# M1_CM4.net
KiCad netlist of a schematic drawn in Altium Designer
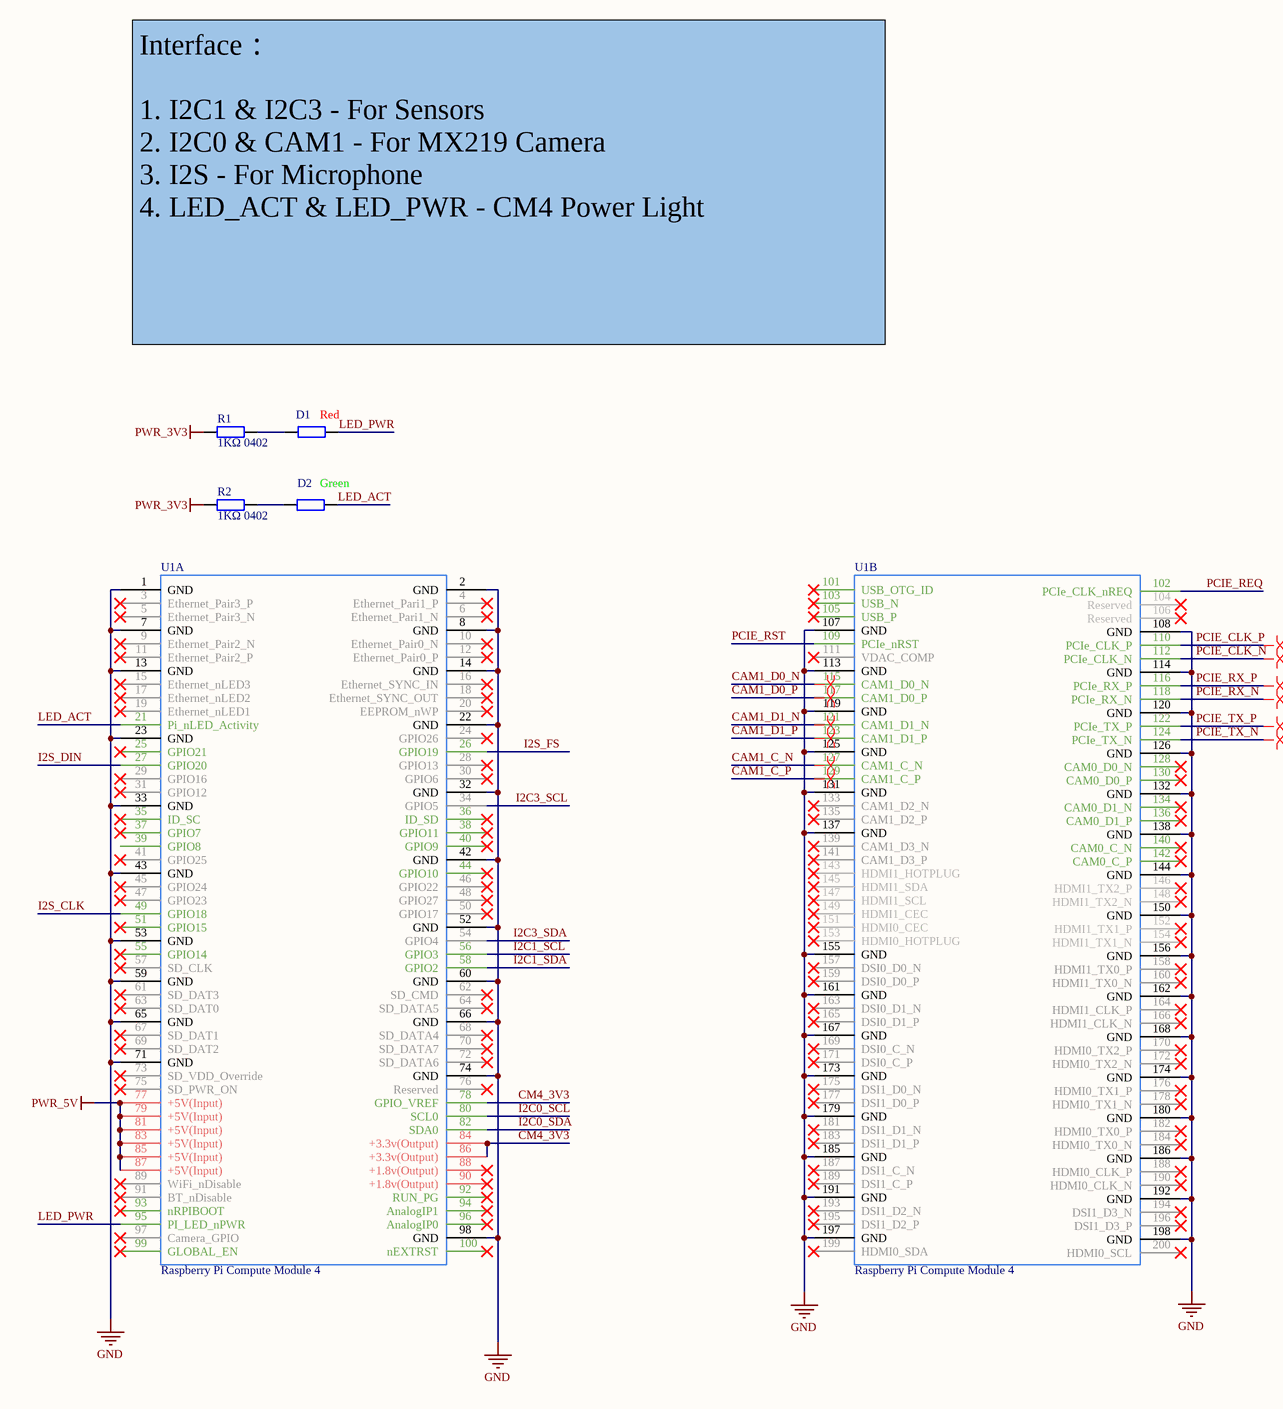
[diagram p0: M1_CM4.SchDoc]

(export (version "E")
  (design (tool "Eeschema 10.0.6"))
  (components
    (comp (ref "D1")
      (value "Red")
      (footprint "0402_R")
      (description "贴片电阻")
      (libsource (lib "Miscellaneous Devices LC") (part "0402 10KΩ (1002) 1%"))
    )
    (comp (ref "D2")
      (value "Green")
      (footprint "0402_R")
      (description "贴片电阻")
      (libsource (lib "Miscellaneous Devices LC") (part "0402 10KΩ (1002) 1%"))
    )
    (comp (ref "R1")
      (value "1KΩ 0402")
      (footprint "0402_R")
      (description "贴片电阻")
      (libsource (lib "Miscellaneous Devices LC") (part "0402 1KΩ (1001) 1%"))
    )
    (comp (ref "R2")
      (value "1KΩ 0402")
      (footprint "0402_R")
      (description "贴片电阻")
      (libsource (lib "Miscellaneous Devices LC") (part "0402 1KΩ (1001) 1%"))
    )
    (comp (ref "U1")
      (value "Raspberry Pi Compute Module 4")
      (footprint "CM4T-DF40HC(3.0)-100DS")
      (libsource (lib "Mars") (part "CM4"))
    )
  )
  (nets
    (net (code "1") (name "/CAM1_C_N") (class "Default")
      (node (ref "U1") (pin "127") (pinfunction "CAM1_C_N_127") (pintype "passive"))
    )
    (net (code "2") (name "/CAM1_C_P") (class "Default")
      (node (ref "U1") (pin "129") (pinfunction "CAM1_C_P_129") (pintype "passive"))
    )
    (net (code "3") (name "/CAM1_D0_N") (class "Default")
      (node (ref "U1") (pin "115") (pinfunction "CAM1_D0_N_115") (pintype "passive"))
    )
    (net (code "4") (name "/CAM1_D0_P") (class "Default")
      (node (ref "U1") (pin "117") (pinfunction "CAM1_D0_P_117") (pintype "passive"))
    )
    (net (code "5") (name "/CAM1_D1_N") (class "Default")
      (node (ref "U1") (pin "121") (pinfunction "CAM1_D1_N_121") (pintype "passive"))
    )
    (net (code "6") (name "/CAM1_D1_P") (class "Default")
      (node (ref "U1") (pin "123") (pinfunction "CAM1_D1_P_123") (pintype "passive"))
    )
    (net (code "7") (name "/CM4_3V3") (class "Default")
      (node (ref "U1") (pin "78") (pinfunction "GPIO_VREF_78") (pintype "passive"))
      (node (ref "U1") (pin "84") (pinfunction "+3.3v(Output)_84") (pintype "passive"))
      (node (ref "U1") (pin "86") (pinfunction "+3.3v(Output)_86") (pintype "passive"))
    )
    (net (code "8") (name "/I2C0_SCL") (class "Default")
      (node (ref "U1") (pin "80") (pinfunction "SCL0_80") (pintype "passive"))
    )
    (net (code "9") (name "/I2C0_SDA") (class "Default")
      (node (ref "U1") (pin "82") (pinfunction "SDA0_82") (pintype "passive"))
    )
    (net (code "10") (name "/I2C1_SCL") (class "Default")
      (node (ref "U1") (pin "56") (pinfunction "GPIO3_56") (pintype "passive"))
    )
    (net (code "11") (name "/I2C1_SDA") (class "Default")
      (node (ref "U1") (pin "58") (pinfunction "GPIO2_58") (pintype "passive"))
    )
    (net (code "12") (name "/I2C3_SCL") (class "Default")
      (node (ref "U1") (pin "34") (pinfunction "GPIO5_34") (pintype "passive"))
    )
    (net (code "13") (name "/I2C3_SDA") (class "Default")
      (node (ref "U1") (pin "54") (pinfunction "GPIO4_54") (pintype "passive"))
    )
    (net (code "14") (name "/I2S_CLK") (class "Default")
      (node (ref "U1") (pin "49") (pinfunction "GPIO18_49") (pintype "passive"))
    )
    (net (code "15") (name "/I2S_DIN") (class "Default")
      (node (ref "U1") (pin "27") (pinfunction "GPIO20_27") (pintype "passive"))
    )
    (net (code "16") (name "/I2S_FS") (class "Default")
      (node (ref "U1") (pin "26") (pinfunction "GPIO19_26") (pintype "passive"))
    )
    (net (code "17") (name "/LED_ACT") (class "Default")
      (node (ref "D2") (pin "2") (pinfunction "2_2") (pintype "passive"))
      (node (ref "U1") (pin "21") (pinfunction "Pi_nLED_Activity_21") (pintype "passive"))
    )
    (net (code "18") (name "/LED_PWR") (class "Default")
      (node (ref "D1") (pin "2") (pinfunction "2_2") (pintype "passive"))
      (node (ref "U1") (pin "95") (pinfunction "PI_LED_nPWR_95") (pintype "passive"))
    )
    (net (code "19") (name "/PCIE_CLK_N") (class "Default")
      (node (ref "U1") (pin "112") (pinfunction "PCIe_CLK_N_112") (pintype "passive"))
    )
    (net (code "20") (name "/PCIE_CLK_P") (class "Default")
      (node (ref "U1") (pin "110") (pinfunction "PCIe_CLK_P_110") (pintype "passive"))
    )
    (net (code "21") (name "/PCIE_REQ") (class "Default")
      (node (ref "U1") (pin "102") (pinfunction "PCIe_CLK_nREQ_102") (pintype "passive"))
    )
    (net (code "22") (name "/PCIE_RST") (class "Default")
      (node (ref "U1") (pin "109") (pinfunction "PCIe_nRST_109") (pintype "passive"))
    )
    (net (code "23") (name "/PCIE_RX_N") (class "Default")
      (node (ref "U1") (pin "118") (pinfunction "PCIe_RX_N_118") (pintype "passive"))
    )
    (net (code "24") (name "/PCIE_RX_P") (class "Default")
      (node (ref "U1") (pin "116") (pinfunction "PCIe_RX_P_116") (pintype "passive"))
    )
    (net (code "25") (name "/PCIE_TX_N") (class "Default")
      (node (ref "U1") (pin "124") (pinfunction "PCIe_TX_N_124") (pintype "passive"))
    )
    (net (code "26") (name "/PCIE_TX_P") (class "Default")
      (node (ref "U1") (pin "122") (pinfunction "PCIe_TX_P_122") (pintype "passive"))
    )
    (net (code "27") (name "GND") (class "Default")
      (node (ref "U1") (pin "1") (pinfunction "GND_1") (pintype "passive"))
      (node (ref "U1") (pin "107") (pinfunction "GND_107") (pintype "passive"))
      (node (ref "U1") (pin "108") (pinfunction "GND_108") (pintype "passive"))
      (node (ref "U1") (pin "113") (pinfunction "GND_113") (pintype "passive"))
      (node (ref "U1") (pin "114") (pinfunction "GND_114") (pintype "passive"))
      (node (ref "U1") (pin "119") (pinfunction "GND_119") (pintype "passive"))
      (node (ref "U1") (pin "120") (pinfunction "GND_120") (pintype "passive"))
      (node (ref "U1") (pin "125") (pinfunction "GND_125") (pintype "passive"))
      (node (ref "U1") (pin "126") (pinfunction "GND_126") (pintype "passive"))
      (node (ref "U1") (pin "13") (pinfunction "GND_13") (pintype "passive"))
      (node (ref "U1") (pin "131") (pinfunction "GND_131") (pintype "passive"))
      (node (ref "U1") (pin "132") (pinfunction "GND_132") (pintype "passive"))
      (node (ref "U1") (pin "137") (pinfunction "GND_137") (pintype "passive"))
      (node (ref "U1") (pin "138") (pinfunction "GND_138") (pintype "passive"))
      (node (ref "U1") (pin "14") (pinfunction "GND_14") (pintype "passive"))
      (node (ref "U1") (pin "144") (pinfunction "GND_144") (pintype "passive"))
      (node (ref "U1") (pin "150") (pinfunction "GND_150") (pintype "passive"))
      (node (ref "U1") (pin "155") (pinfunction "GND_155") (pintype "passive"))
      (node (ref "U1") (pin "156") (pinfunction "GND_156") (pintype "passive"))
      (node (ref "U1") (pin "161") (pinfunction "GND_161") (pintype "passive"))
      (node (ref "U1") (pin "162") (pinfunction "GND_162") (pintype "passive"))
      (node (ref "U1") (pin "167") (pinfunction "GND_167") (pintype "passive"))
      (node (ref "U1") (pin "168") (pinfunction "GND_168") (pintype "passive"))
      (node (ref "U1") (pin "173") (pinfunction "GND_173") (pintype "passive"))
      (node (ref "U1") (pin "174") (pinfunction "GND_174") (pintype "passive"))
      (node (ref "U1") (pin "179") (pinfunction "GND_179") (pintype "passive"))
      (node (ref "U1") (pin "180") (pinfunction "GND_180") (pintype "passive"))
      (node (ref "U1") (pin "185") (pinfunction "GND_185") (pintype "passive"))
      (node (ref "U1") (pin "186") (pinfunction "GND_186") (pintype "passive"))
      (node (ref "U1") (pin "191") (pinfunction "GND_191") (pintype "passive"))
      (node (ref "U1") (pin "192") (pinfunction "GND_192") (pintype "passive"))
      (node (ref "U1") (pin "197") (pinfunction "GND_197") (pintype "passive"))
      (node (ref "U1") (pin "198") (pinfunction "GND_198") (pintype "passive"))
      (node (ref "U1") (pin "2") (pinfunction "GND_2") (pintype "passive"))
      (node (ref "U1") (pin "22") (pinfunction "GND_22") (pintype "passive"))
      (node (ref "U1") (pin "23") (pinfunction "GND_23") (pintype "passive"))
      (node (ref "U1") (pin "32") (pinfunction "GND_32") (pintype "passive"))
      (node (ref "U1") (pin "33") (pinfunction "GND_33") (pintype "passive"))
      (node (ref "U1") (pin "42") (pinfunction "GND_42") (pintype "passive"))
      (node (ref "U1") (pin "43") (pinfunction "GND_43") (pintype "passive"))
      (node (ref "U1") (pin "52") (pinfunction "GND_52") (pintype "passive"))
      (node (ref "U1") (pin "53") (pinfunction "GND_53") (pintype "passive"))
      (node (ref "U1") (pin "59") (pinfunction "GND_59") (pintype "passive"))
      (node (ref "U1") (pin "60") (pinfunction "GND_60") (pintype "passive"))
      (node (ref "U1") (pin "65") (pinfunction "GND_65") (pintype "passive"))
      (node (ref "U1") (pin "66") (pinfunction "GND_66") (pintype "passive"))
      (node (ref "U1") (pin "7") (pinfunction "GND_7") (pintype "passive"))
      (node (ref "U1") (pin "71") (pinfunction "GND_71") (pintype "passive"))
      (node (ref "U1") (pin "74") (pinfunction "GND_74") (pintype "passive"))
      (node (ref "U1") (pin "8") (pinfunction "GND_8") (pintype "passive"))
      (node (ref "U1") (pin "98") (pinfunction "GND_98") (pintype "passive"))
    )
    (net (code "28") (name "Net-(D1-Pad1)") (class "Default")
      (node (ref "D1") (pin "1") (pinfunction "1_1") (pintype "passive"))
      (node (ref "R1") (pin "2") (pinfunction "2_2") (pintype "passive"))
    )
    (net (code "29") (name "Net-(D2-Pad1)") (class "Default")
      (node (ref "D2") (pin "1") (pinfunction "1_1") (pintype "passive"))
      (node (ref "R2") (pin "2") (pinfunction "2_2") (pintype "passive"))
    )
    (net (code "30") (name "PWR_3V3") (class "Default")
      (node (ref "R1") (pin "1") (pinfunction "1_1") (pintype "passive"))
      (node (ref "R2") (pin "1") (pinfunction "1_1") (pintype "passive"))
    )
    (net (code "31") (name "PWR_5V") (class "Default")
      (node (ref "U1") (pin "77") (pinfunction "+5V(Input)_77") (pintype "passive"))
      (node (ref "U1") (pin "79") (pinfunction "+5V(Input)_79") (pintype "passive"))
      (node (ref "U1") (pin "81") (pinfunction "+5V(Input)_81") (pintype "passive"))
      (node (ref "U1") (pin "83") (pinfunction "+5V(Input)_83") (pintype "passive"))
      (node (ref "U1") (pin "85") (pinfunction "+5V(Input)_85") (pintype "passive"))
      (node (ref "U1") (pin "87") (pinfunction "+5V(Input)_87") (pintype "passive"))
    )
    (net (code "32") (name "unconnected-(U1A-+1.8v(Output)-Pad88)") (class "Default")
      (node (ref "U1") (pin "88") (pinfunction "+1.8v(Output)_88") (pintype "passive+no_connect"))
    )
    (net (code "33") (name "unconnected-(U1A-+1.8v(Output)-Pad90)") (class "Default")
      (node (ref "U1") (pin "90") (pinfunction "+1.8v(Output)_90") (pintype "passive+no_connect"))
    )
    (net (code "34") (name "unconnected-(U1A-AnalogIP0-Pad96)") (class "Default")
      (node (ref "U1") (pin "96") (pinfunction "AnalogIP0_96") (pintype "passive+no_connect"))
    )
    (net (code "35") (name "unconnected-(U1A-AnalogIP1-Pad94)") (class "Default")
      (node (ref "U1") (pin "94") (pinfunction "AnalogIP1_94") (pintype "passive+no_connect"))
    )
    (net (code "36") (name "unconnected-(U1A-BT_nDisable-Pad91)") (class "Default")
      (node (ref "U1") (pin "91") (pinfunction "BT_nDisable_91") (pintype "passive+no_connect"))
    )
    (net (code "37") (name "unconnected-(U1A-Camera_GPIO-Pad97)") (class "Default")
      (node (ref "U1") (pin "97") (pinfunction "Camera_GPIO_97") (pintype "passive+no_connect"))
    )
    (net (code "38") (name "unconnected-(U1A-EEPROM_nWP-Pad20)") (class "Default")
      (node (ref "U1") (pin "20") (pinfunction "EEPROM_nWP_20") (pintype "passive+no_connect"))
    )
    (net (code "39") (name "unconnected-(U1A-Ethernet_Pair0_N-Pad10)") (class "Default")
      (node (ref "U1") (pin "10") (pinfunction "Ethernet_Pair0_N_10") (pintype "passive+no_connect"))
    )
    (net (code "40") (name "unconnected-(U1A-Ethernet_Pair0_P-Pad12)") (class "Default")
      (node (ref "U1") (pin "12") (pinfunction "Ethernet_Pair0_P_12") (pintype "passive+no_connect"))
    )
    (net (code "41") (name "unconnected-(U1A-Ethernet_Pair2_N-Pad9)") (class "Default")
      (node (ref "U1") (pin "9") (pinfunction "Ethernet_Pair2_N_9") (pintype "passive+no_connect"))
    )
    (net (code "42") (name "unconnected-(U1A-Ethernet_Pair2_P-Pad11)") (class "Default")
      (node (ref "U1") (pin "11") (pinfunction "Ethernet_Pair2_P_11") (pintype "passive+no_connect"))
    )
    (net (code "43") (name "unconnected-(U1A-Ethernet_Pair3_N-Pad5)") (class "Default")
      (node (ref "U1") (pin "5") (pinfunction "Ethernet_Pair3_N_5") (pintype "passive+no_connect"))
    )
    (net (code "44") (name "unconnected-(U1A-Ethernet_Pair3_P-Pad3)") (class "Default")
      (node (ref "U1") (pin "3") (pinfunction "Ethernet_Pair3_P_3") (pintype "passive+no_connect"))
    )
    (net (code "45") (name "unconnected-(U1A-Ethernet_Pari1_N-Pad6)") (class "Default")
      (node (ref "U1") (pin "6") (pinfunction "Ethernet_Pari1_N_6") (pintype "passive+no_connect"))
    )
    (net (code "46") (name "unconnected-(U1A-Ethernet_Pari1_P-Pad4)") (class "Default")
      (node (ref "U1") (pin "4") (pinfunction "Ethernet_Pari1_P_4") (pintype "passive+no_connect"))
    )
    (net (code "47") (name "unconnected-(U1A-Ethernet_SYNC_IN-Pad16)") (class "Default")
      (node (ref "U1") (pin "16") (pinfunction "Ethernet_SYNC_IN_16") (pintype "passive+no_connect"))
    )
    (net (code "48") (name "unconnected-(U1A-Ethernet_SYNC_OUT-Pad18)") (class "Default")
      (node (ref "U1") (pin "18") (pinfunction "Ethernet_SYNC_OUT_18") (pintype "passive+no_connect"))
    )
    (net (code "49") (name "unconnected-(U1A-Ethernet_nLED1-Pad19)") (class "Default")
      (node (ref "U1") (pin "19") (pinfunction "Ethernet_nLED1_19") (pintype "passive+no_connect"))
    )
    (net (code "50") (name "unconnected-(U1A-Ethernet_nLED2-Pad17)") (class "Default")
      (node (ref "U1") (pin "17") (pinfunction "Ethernet_nLED2_17") (pintype "passive+no_connect"))
    )
    (net (code "51") (name "unconnected-(U1A-Ethernet_nLED3-Pad15)") (class "Default")
      (node (ref "U1") (pin "15") (pinfunction "Ethernet_nLED3_15") (pintype "passive+no_connect"))
    )
    (net (code "52") (name "unconnected-(U1A-GLOBAL_EN-Pad99)") (class "Default")
      (node (ref "U1") (pin "99") (pinfunction "GLOBAL_EN_99") (pintype "passive+no_connect"))
    )
    (net (code "53") (name "unconnected-(U1A-GPIO6-Pad30)") (class "Default")
      (node (ref "U1") (pin "30") (pinfunction "GPIO6_30") (pintype "passive+no_connect"))
    )
    (net (code "54") (name "unconnected-(U1A-GPIO7-Pad37)") (class "Default")
      (node (ref "U1") (pin "37") (pinfunction "GPIO7_37") (pintype "passive+no_connect"))
    )
    (net (code "55") (name "unconnected-(U1A-GPIO8-Pad39)") (class "Default")
      (node (ref "U1") (pin "39") (pinfunction "GPIO8_39") (pintype "passive"))
    )
    (net (code "56") (name "unconnected-(U1A-GPIO9-Pad40)") (class "Default")
      (node (ref "U1") (pin "40") (pinfunction "GPIO9_40") (pintype "passive+no_connect"))
    )
    (net (code "57") (name "unconnected-(U1A-GPIO10-Pad44)") (class "Default")
      (node (ref "U1") (pin "44") (pinfunction "GPIO10_44") (pintype "passive+no_connect"))
    )
    (net (code "58") (name "unconnected-(U1A-GPIO11-Pad38)") (class "Default")
      (node (ref "U1") (pin "38") (pinfunction "GPIO11_38") (pintype "passive+no_connect"))
    )
    (net (code "59") (name "unconnected-(U1A-GPIO12-Pad31)") (class "Default")
      (node (ref "U1") (pin "31") (pinfunction "GPIO12_31") (pintype "passive+no_connect"))
    )
    (net (code "60") (name "unconnected-(U1A-GPIO13-Pad28)") (class "Default")
      (node (ref "U1") (pin "28") (pinfunction "GPIO13_28") (pintype "passive+no_connect"))
    )
    (net (code "61") (name "unconnected-(U1A-GPIO14-Pad55)") (class "Default")
      (node (ref "U1") (pin "55") (pinfunction "GPIO14_55") (pintype "passive+no_connect"))
    )
    (net (code "62") (name "unconnected-(U1A-GPIO15-Pad51)") (class "Default")
      (node (ref "U1") (pin "51") (pinfunction "GPIO15_51") (pintype "passive+no_connect"))
    )
    (net (code "63") (name "unconnected-(U1A-GPIO16-Pad29)") (class "Default")
      (node (ref "U1") (pin "29") (pinfunction "GPIO16_29") (pintype "passive+no_connect"))
    )
    (net (code "64") (name "unconnected-(U1A-GPIO17-Pad50)") (class "Default")
      (node (ref "U1") (pin "50") (pinfunction "GPIO17_50") (pintype "passive+no_connect"))
    )
    (net (code "65") (name "unconnected-(U1A-GPIO21-Pad25)") (class "Default")
      (node (ref "U1") (pin "25") (pinfunction "GPIO21_25") (pintype "passive+no_connect"))
    )
    (net (code "66") (name "unconnected-(U1A-GPIO22-Pad46)") (class "Default")
      (node (ref "U1") (pin "46") (pinfunction "GPIO22_46") (pintype "passive+no_connect"))
    )
    (net (code "67") (name "unconnected-(U1A-GPIO23-Pad47)") (class "Default")
      (node (ref "U1") (pin "47") (pinfunction "GPIO23_47") (pintype "passive+no_connect"))
    )
    (net (code "68") (name "unconnected-(U1A-GPIO24-Pad45)") (class "Default")
      (node (ref "U1") (pin "45") (pinfunction "GPIO24_45") (pintype "passive+no_connect"))
    )
    (net (code "69") (name "unconnected-(U1A-GPIO25-Pad41)") (class "Default")
      (node (ref "U1") (pin "41") (pinfunction "GPIO25_41") (pintype "passive+no_connect"))
    )
    (net (code "70") (name "unconnected-(U1A-GPIO26-Pad24)") (class "Default")
      (node (ref "U1") (pin "24") (pinfunction "GPIO26_24") (pintype "passive+no_connect"))
    )
    (net (code "71") (name "unconnected-(U1A-GPIO27-Pad48)") (class "Default")
      (node (ref "U1") (pin "48") (pinfunction "GPIO27_48") (pintype "passive+no_connect"))
    )
    (net (code "72") (name "unconnected-(U1A-ID_SC-Pad35)") (class "Default")
      (node (ref "U1") (pin "35") (pinfunction "ID_SC_35") (pintype "passive+no_connect"))
    )
    (net (code "73") (name "unconnected-(U1A-ID_SD-Pad36)") (class "Default")
      (node (ref "U1") (pin "36") (pinfunction "ID_SD_36") (pintype "passive+no_connect"))
    )
    (net (code "74") (name "unconnected-(U1A-RUN_PG-Pad92)") (class "Default")
      (node (ref "U1") (pin "92") (pinfunction "RUN_PG_92") (pintype "passive+no_connect"))
    )
    (net (code "75") (name "unconnected-(U1A-Reserved-Pad76)") (class "Default")
      (node (ref "U1") (pin "76") (pinfunction "Reserved_76") (pintype "passive+no_connect"))
    )
    (net (code "76") (name "unconnected-(U1A-SD_CLK-Pad57)") (class "Default")
      (node (ref "U1") (pin "57") (pinfunction "SD_CLK_57") (pintype "passive+no_connect"))
    )
    (net (code "77") (name "unconnected-(U1A-SD_CMD-Pad62)") (class "Default")
      (node (ref "U1") (pin "62") (pinfunction "SD_CMD_62") (pintype "passive+no_connect"))
    )
    (net (code "78") (name "unconnected-(U1A-SD_DAT0-Pad63)") (class "Default")
      (node (ref "U1") (pin "63") (pinfunction "SD_DAT0_63") (pintype "passive+no_connect"))
    )
    (net (code "79") (name "unconnected-(U1A-SD_DAT1-Pad67)") (class "Default")
      (node (ref "U1") (pin "67") (pinfunction "SD_DAT1_67") (pintype "passive+no_connect"))
    )
    (net (code "80") (name "unconnected-(U1A-SD_DAT2-Pad69)") (class "Default")
      (node (ref "U1") (pin "69") (pinfunction "SD_DAT2_69") (pintype "passive+no_connect"))
    )
    (net (code "81") (name "unconnected-(U1A-SD_DAT3-Pad61)") (class "Default")
      (node (ref "U1") (pin "61") (pinfunction "SD_DAT3_61") (pintype "passive+no_connect"))
    )
    (net (code "82") (name "unconnected-(U1A-SD_DATA4-Pad68)") (class "Default")
      (node (ref "U1") (pin "68") (pinfunction "SD_DATA4_68") (pintype "passive+no_connect"))
    )
    (net (code "83") (name "unconnected-(U1A-SD_DATA5-Pad64)") (class "Default")
      (node (ref "U1") (pin "64") (pinfunction "SD_DATA5_64") (pintype "passive+no_connect"))
    )
    (net (code "84") (name "unconnected-(U1A-SD_DATA6-Pad72)") (class "Default")
      (node (ref "U1") (pin "72") (pinfunction "SD_DATA6_72") (pintype "passive+no_connect"))
    )
    (net (code "85") (name "unconnected-(U1A-SD_DATA7-Pad70)") (class "Default")
      (node (ref "U1") (pin "70") (pinfunction "SD_DATA7_70") (pintype "passive+no_connect"))
    )
    (net (code "86") (name "unconnected-(U1A-SD_PWR_ON-Pad75)") (class "Default")
      (node (ref "U1") (pin "75") (pinfunction "SD_PWR_ON_75") (pintype "passive+no_connect"))
    )
    (net (code "87") (name "unconnected-(U1A-SD_VDD_Override-Pad73)") (class "Default")
      (node (ref "U1") (pin "73") (pinfunction "SD_VDD_Override_73") (pintype "passive+no_connect"))
    )
    (net (code "88") (name "unconnected-(U1A-WiFi_nDisable-Pad89)") (class "Default")
      (node (ref "U1") (pin "89") (pinfunction "WiFi_nDisable_89") (pintype "passive+no_connect"))
    )
    (net (code "89") (name "unconnected-(U1A-nEXTRST-Pad100)") (class "Default")
      (node (ref "U1") (pin "100") (pinfunction "nEXTRST_100") (pintype "passive+no_connect"))
    )
    (net (code "90") (name "unconnected-(U1A-nRPIBOOT-Pad93)") (class "Default")
      (node (ref "U1") (pin "93") (pinfunction "nRPIBOOT_93") (pintype "passive+no_connect"))
    )
    (net (code "91") (name "unconnected-(U1B-CAM0_C_N-Pad140)") (class "Default")
      (node (ref "U1") (pin "140") (pinfunction "CAM0_C_N_140") (pintype "passive+no_connect"))
    )
    (net (code "92") (name "unconnected-(U1B-CAM0_C_P-Pad142)") (class "Default")
      (node (ref "U1") (pin "142") (pinfunction "CAM0_C_P_142") (pintype "passive+no_connect"))
    )
    (net (code "93") (name "unconnected-(U1B-CAM0_D0_N-Pad128)") (class "Default")
      (node (ref "U1") (pin "128") (pinfunction "CAM0_D0_N_128") (pintype "passive+no_connect"))
    )
    (net (code "94") (name "unconnected-(U1B-CAM0_D0_P-Pad130)") (class "Default")
      (node (ref "U1") (pin "130") (pinfunction "CAM0_D0_P_130") (pintype "passive+no_connect"))
    )
    (net (code "95") (name "unconnected-(U1B-CAM0_D1_N-Pad134)") (class "Default")
      (node (ref "U1") (pin "134") (pinfunction "CAM0_D1_N_134") (pintype "passive+no_connect"))
    )
    (net (code "96") (name "unconnected-(U1B-CAM0_D1_P-Pad136)") (class "Default")
      (node (ref "U1") (pin "136") (pinfunction "CAM0_D1_P_136") (pintype "passive+no_connect"))
    )
    (net (code "97") (name "unconnected-(U1B-CAM1_D2_N-Pad133)") (class "Default")
      (node (ref "U1") (pin "133") (pinfunction "CAM1_D2_N_133") (pintype "passive+no_connect"))
    )
    (net (code "98") (name "unconnected-(U1B-CAM1_D2_P-Pad135)") (class "Default")
      (node (ref "U1") (pin "135") (pinfunction "CAM1_D2_P_135") (pintype "passive+no_connect"))
    )
    (net (code "99") (name "unconnected-(U1B-CAM1_D3_N-Pad139)") (class "Default")
      (node (ref "U1") (pin "139") (pinfunction "CAM1_D3_N_139") (pintype "passive+no_connect"))
    )
    (net (code "100") (name "unconnected-(U1B-CAM1_D3_P-Pad141)") (class "Default")
      (node (ref "U1") (pin "141") (pinfunction "CAM1_D3_P_141") (pintype "passive+no_connect"))
    )
    (net (code "101") (name "unconnected-(U1B-DSI0_C_N-Pad169)") (class "Default")
      (node (ref "U1") (pin "169") (pinfunction "DSI0_C_N_169") (pintype "passive+no_connect"))
    )
    (net (code "102") (name "unconnected-(U1B-DSI0_C_P-Pad171)") (class "Default")
      (node (ref "U1") (pin "171") (pinfunction "DSI0_C_P_171") (pintype "passive+no_connect"))
    )
    (net (code "103") (name "unconnected-(U1B-DSI0_D0_N-Pad157)") (class "Default")
      (node (ref "U1") (pin "157") (pinfunction "DSI0_D0_N_157") (pintype "passive+no_connect"))
    )
    (net (code "104") (name "unconnected-(U1B-DSI0_D0_P-Pad159)") (class "Default")
      (node (ref "U1") (pin "159") (pinfunction "DSI0_D0_P_159") (pintype "passive+no_connect"))
    )
    (net (code "105") (name "unconnected-(U1B-DSI0_D1_N-Pad163)") (class "Default")
      (node (ref "U1") (pin "163") (pinfunction "DSI0_D1_N_163") (pintype "passive+no_connect"))
    )
    (net (code "106") (name "unconnected-(U1B-DSI0_D1_P-Pad165)") (class "Default")
      (node (ref "U1") (pin "165") (pinfunction "DSI0_D1_P_165") (pintype "passive+no_connect"))
    )
    (net (code "107") (name "unconnected-(U1B-DSI1_C_N-Pad187)") (class "Default")
      (node (ref "U1") (pin "187") (pinfunction "DSI1_C_N_187") (pintype "passive+no_connect"))
    )
    (net (code "108") (name "unconnected-(U1B-DSI1_C_P-Pad189)") (class "Default")
      (node (ref "U1") (pin "189") (pinfunction "DSI1_C_P_189") (pintype "passive+no_connect"))
    )
    (net (code "109") (name "unconnected-(U1B-DSI1_D0_N-Pad175)") (class "Default")
      (node (ref "U1") (pin "175") (pinfunction "DSI1_D0_N_175") (pintype "passive+no_connect"))
    )
    (net (code "110") (name "unconnected-(U1B-DSI1_D0_P-Pad177)") (class "Default")
      (node (ref "U1") (pin "177") (pinfunction "DSI1_D0_P_177") (pintype "passive+no_connect"))
    )
    (net (code "111") (name "unconnected-(U1B-DSI1_D1_N-Pad181)") (class "Default")
      (node (ref "U1") (pin "181") (pinfunction "DSI1_D1_N_181") (pintype "passive+no_connect"))
    )
    (net (code "112") (name "unconnected-(U1B-DSI1_D1_P-Pad183)") (class "Default")
      (node (ref "U1") (pin "183") (pinfunction "DSI1_D1_P_183") (pintype "passive+no_connect"))
    )
    (net (code "113") (name "unconnected-(U1B-DSI1_D2_N-Pad193)") (class "Default")
      (node (ref "U1") (pin "193") (pinfunction "DSI1_D2_N_193") (pintype "passive+no_connect"))
    )
    (net (code "114") (name "unconnected-(U1B-DSI1_D2_P-Pad195)") (class "Default")
      (node (ref "U1") (pin "195") (pinfunction "DSI1_D2_P_195") (pintype "passive+no_connect"))
    )
    (net (code "115") (name "unconnected-(U1B-DSI1_D3_N-Pad194)") (class "Default")
      (node (ref "U1") (pin "194") (pinfunction "DSI1_D3_N_194") (pintype "passive+no_connect"))
    )
    (net (code "116") (name "unconnected-(U1B-DSI1_D3_P-Pad196)") (class "Default")
      (node (ref "U1") (pin "196") (pinfunction "DSI1_D3_P_196") (pintype "passive+no_connect"))
    )
    (net (code "117") (name "unconnected-(U1B-HDMI0_CEC-Pad151)") (class "Default")
      (node (ref "U1") (pin "151") (pinfunction "HDMI0_CEC_151") (pintype "passive+no_connect"))
    )
    (net (code "118") (name "unconnected-(U1B-HDMI0_CLK_N-Pad190)") (class "Default")
      (node (ref "U1") (pin "190") (pinfunction "HDMI0_CLK_N_190") (pintype "passive+no_connect"))
    )
    (net (code "119") (name "unconnected-(U1B-HDMI0_CLK_P-Pad188)") (class "Default")
      (node (ref "U1") (pin "188") (pinfunction "HDMI0_CLK_P_188") (pintype "passive+no_connect"))
    )
    (net (code "120") (name "unconnected-(U1B-HDMI0_HOTPLUG-Pad153)") (class "Default")
      (node (ref "U1") (pin "153") (pinfunction "HDMI0_HOTPLUG_153") (pintype "passive+no_connect"))
    )
    (net (code "121") (name "unconnected-(U1B-HDMI0_SCL-Pad200)") (class "Default")
      (node (ref "U1") (pin "200") (pinfunction "HDMI0_SCL_200") (pintype "passive+no_connect"))
    )
    (net (code "122") (name "unconnected-(U1B-HDMI0_SDA-Pad199)") (class "Default")
      (node (ref "U1") (pin "199") (pinfunction "HDMI0_SDA_199") (pintype "passive+no_connect"))
    )
    (net (code "123") (name "unconnected-(U1B-HDMI0_TX0_N-Pad184)") (class "Default")
      (node (ref "U1") (pin "184") (pinfunction "HDMI0_TX0_N_184") (pintype "passive+no_connect"))
    )
    (net (code "124") (name "unconnected-(U1B-HDMI0_TX0_P-Pad182)") (class "Default")
      (node (ref "U1") (pin "182") (pinfunction "HDMI0_TX0_P_182") (pintype "passive+no_connect"))
    )
    (net (code "125") (name "unconnected-(U1B-HDMI0_TX1_N-Pad178)") (class "Default")
      (node (ref "U1") (pin "178") (pinfunction "HDMI0_TX1_N_178") (pintype "passive+no_connect"))
    )
    (net (code "126") (name "unconnected-(U1B-HDMI0_TX1_P-Pad176)") (class "Default")
      (node (ref "U1") (pin "176") (pinfunction "HDMI0_TX1_P_176") (pintype "passive+no_connect"))
    )
    (net (code "127") (name "unconnected-(U1B-HDMI0_TX2_N-Pad172)") (class "Default")
      (node (ref "U1") (pin "172") (pinfunction "HDMI0_TX2_N_172") (pintype "passive+no_connect"))
    )
    (net (code "128") (name "unconnected-(U1B-HDMI0_TX2_P-Pad170)") (class "Default")
      (node (ref "U1") (pin "170") (pinfunction "HDMI0_TX2_P_170") (pintype "passive+no_connect"))
    )
    (net (code "129") (name "unconnected-(U1B-HDMI1_CEC-Pad149)") (class "Default")
      (node (ref "U1") (pin "149") (pinfunction "HDMI1_CEC_149") (pintype "passive+no_connect"))
    )
    (net (code "130") (name "unconnected-(U1B-HDMI1_CLK_N-Pad166)") (class "Default")
      (node (ref "U1") (pin "166") (pinfunction "HDMI1_CLK_N_166") (pintype "passive+no_connect"))
    )
    (net (code "131") (name "unconnected-(U1B-HDMI1_CLK_P-Pad164)") (class "Default")
      (node (ref "U1") (pin "164") (pinfunction "HDMI1_CLK_P_164") (pintype "passive+no_connect"))
    )
    (net (code "132") (name "unconnected-(U1B-HDMI1_HOTPLUG-Pad143)") (class "Default")
      (node (ref "U1") (pin "143") (pinfunction "HDMI1_HOTPLUG_143") (pintype "passive+no_connect"))
    )
    (net (code "133") (name "unconnected-(U1B-HDMI1_SCL-Pad147)") (class "Default")
      (node (ref "U1") (pin "147") (pinfunction "HDMI1_SCL_147") (pintype "passive+no_connect"))
    )
    (net (code "134") (name "unconnected-(U1B-HDMI1_SDA-Pad145)") (class "Default")
      (node (ref "U1") (pin "145") (pinfunction "HDMI1_SDA_145") (pintype "passive+no_connect"))
    )
    (net (code "135") (name "unconnected-(U1B-HDMI1_TX0_N-Pad160)") (class "Default")
      (node (ref "U1") (pin "160") (pinfunction "HDMI1_TX0_N_160") (pintype "passive+no_connect"))
    )
    (net (code "136") (name "unconnected-(U1B-HDMI1_TX0_P-Pad158)") (class "Default")
      (node (ref "U1") (pin "158") (pinfunction "HDMI1_TX0_P_158") (pintype "passive+no_connect"))
    )
    (net (code "137") (name "unconnected-(U1B-HDMI1_TX1_N-Pad154)") (class "Default")
      (node (ref "U1") (pin "154") (pinfunction "HDMI1_TX1_N_154") (pintype "passive+no_connect"))
    )
    (net (code "138") (name "unconnected-(U1B-HDMI1_TX1_P-Pad152)") (class "Default")
      (node (ref "U1") (pin "152") (pinfunction "HDMI1_TX1_P_152") (pintype "passive+no_connect"))
    )
    (net (code "139") (name "unconnected-(U1B-HDMI1_TX2_N-Pad148)") (class "Default")
      (node (ref "U1") (pin "148") (pinfunction "HDMI1_TX2_N_148") (pintype "passive+no_connect"))
    )
    (net (code "140") (name "unconnected-(U1B-HDMI1_TX2_P-Pad146)") (class "Default")
      (node (ref "U1") (pin "146") (pinfunction "HDMI1_TX2_P_146") (pintype "passive+no_connect"))
    )
    (net (code "141") (name "unconnected-(U1B-Reserved-Pad104)") (class "Default")
      (node (ref "U1") (pin "104") (pinfunction "Reserved_104") (pintype "passive+no_connect"))
    )
    (net (code "142") (name "unconnected-(U1B-Reserved-Pad106)") (class "Default")
      (node (ref "U1") (pin "106") (pinfunction "Reserved_106") (pintype "passive+no_connect"))
    )
    (net (code "143") (name "unconnected-(U1B-USB_N-Pad103)") (class "Default")
      (node (ref "U1") (pin "103") (pinfunction "USB_N_103") (pintype "passive+no_connect"))
    )
    (net (code "144") (name "unconnected-(U1B-USB_OTG_ID-Pad101)") (class "Default")
      (node (ref "U1") (pin "101") (pinfunction "USB_OTG_ID_101") (pintype "passive+no_connect"))
    )
    (net (code "145") (name "unconnected-(U1B-USB_P-Pad105)") (class "Default")
      (node (ref "U1") (pin "105") (pinfunction "USB_P_105") (pintype "passive+no_connect"))
    )
    (net (code "146") (name "unconnected-(U1B-VDAC_COMP-Pad111)") (class "Default")
      (node (ref "U1") (pin "111") (pinfunction "VDAC_COMP_111") (pintype "passive+no_connect"))
    )
  )
)
